# 1-Schematic_EmbeddedLab.net
KiCad netlist of a schematic drawn in EasyEDA
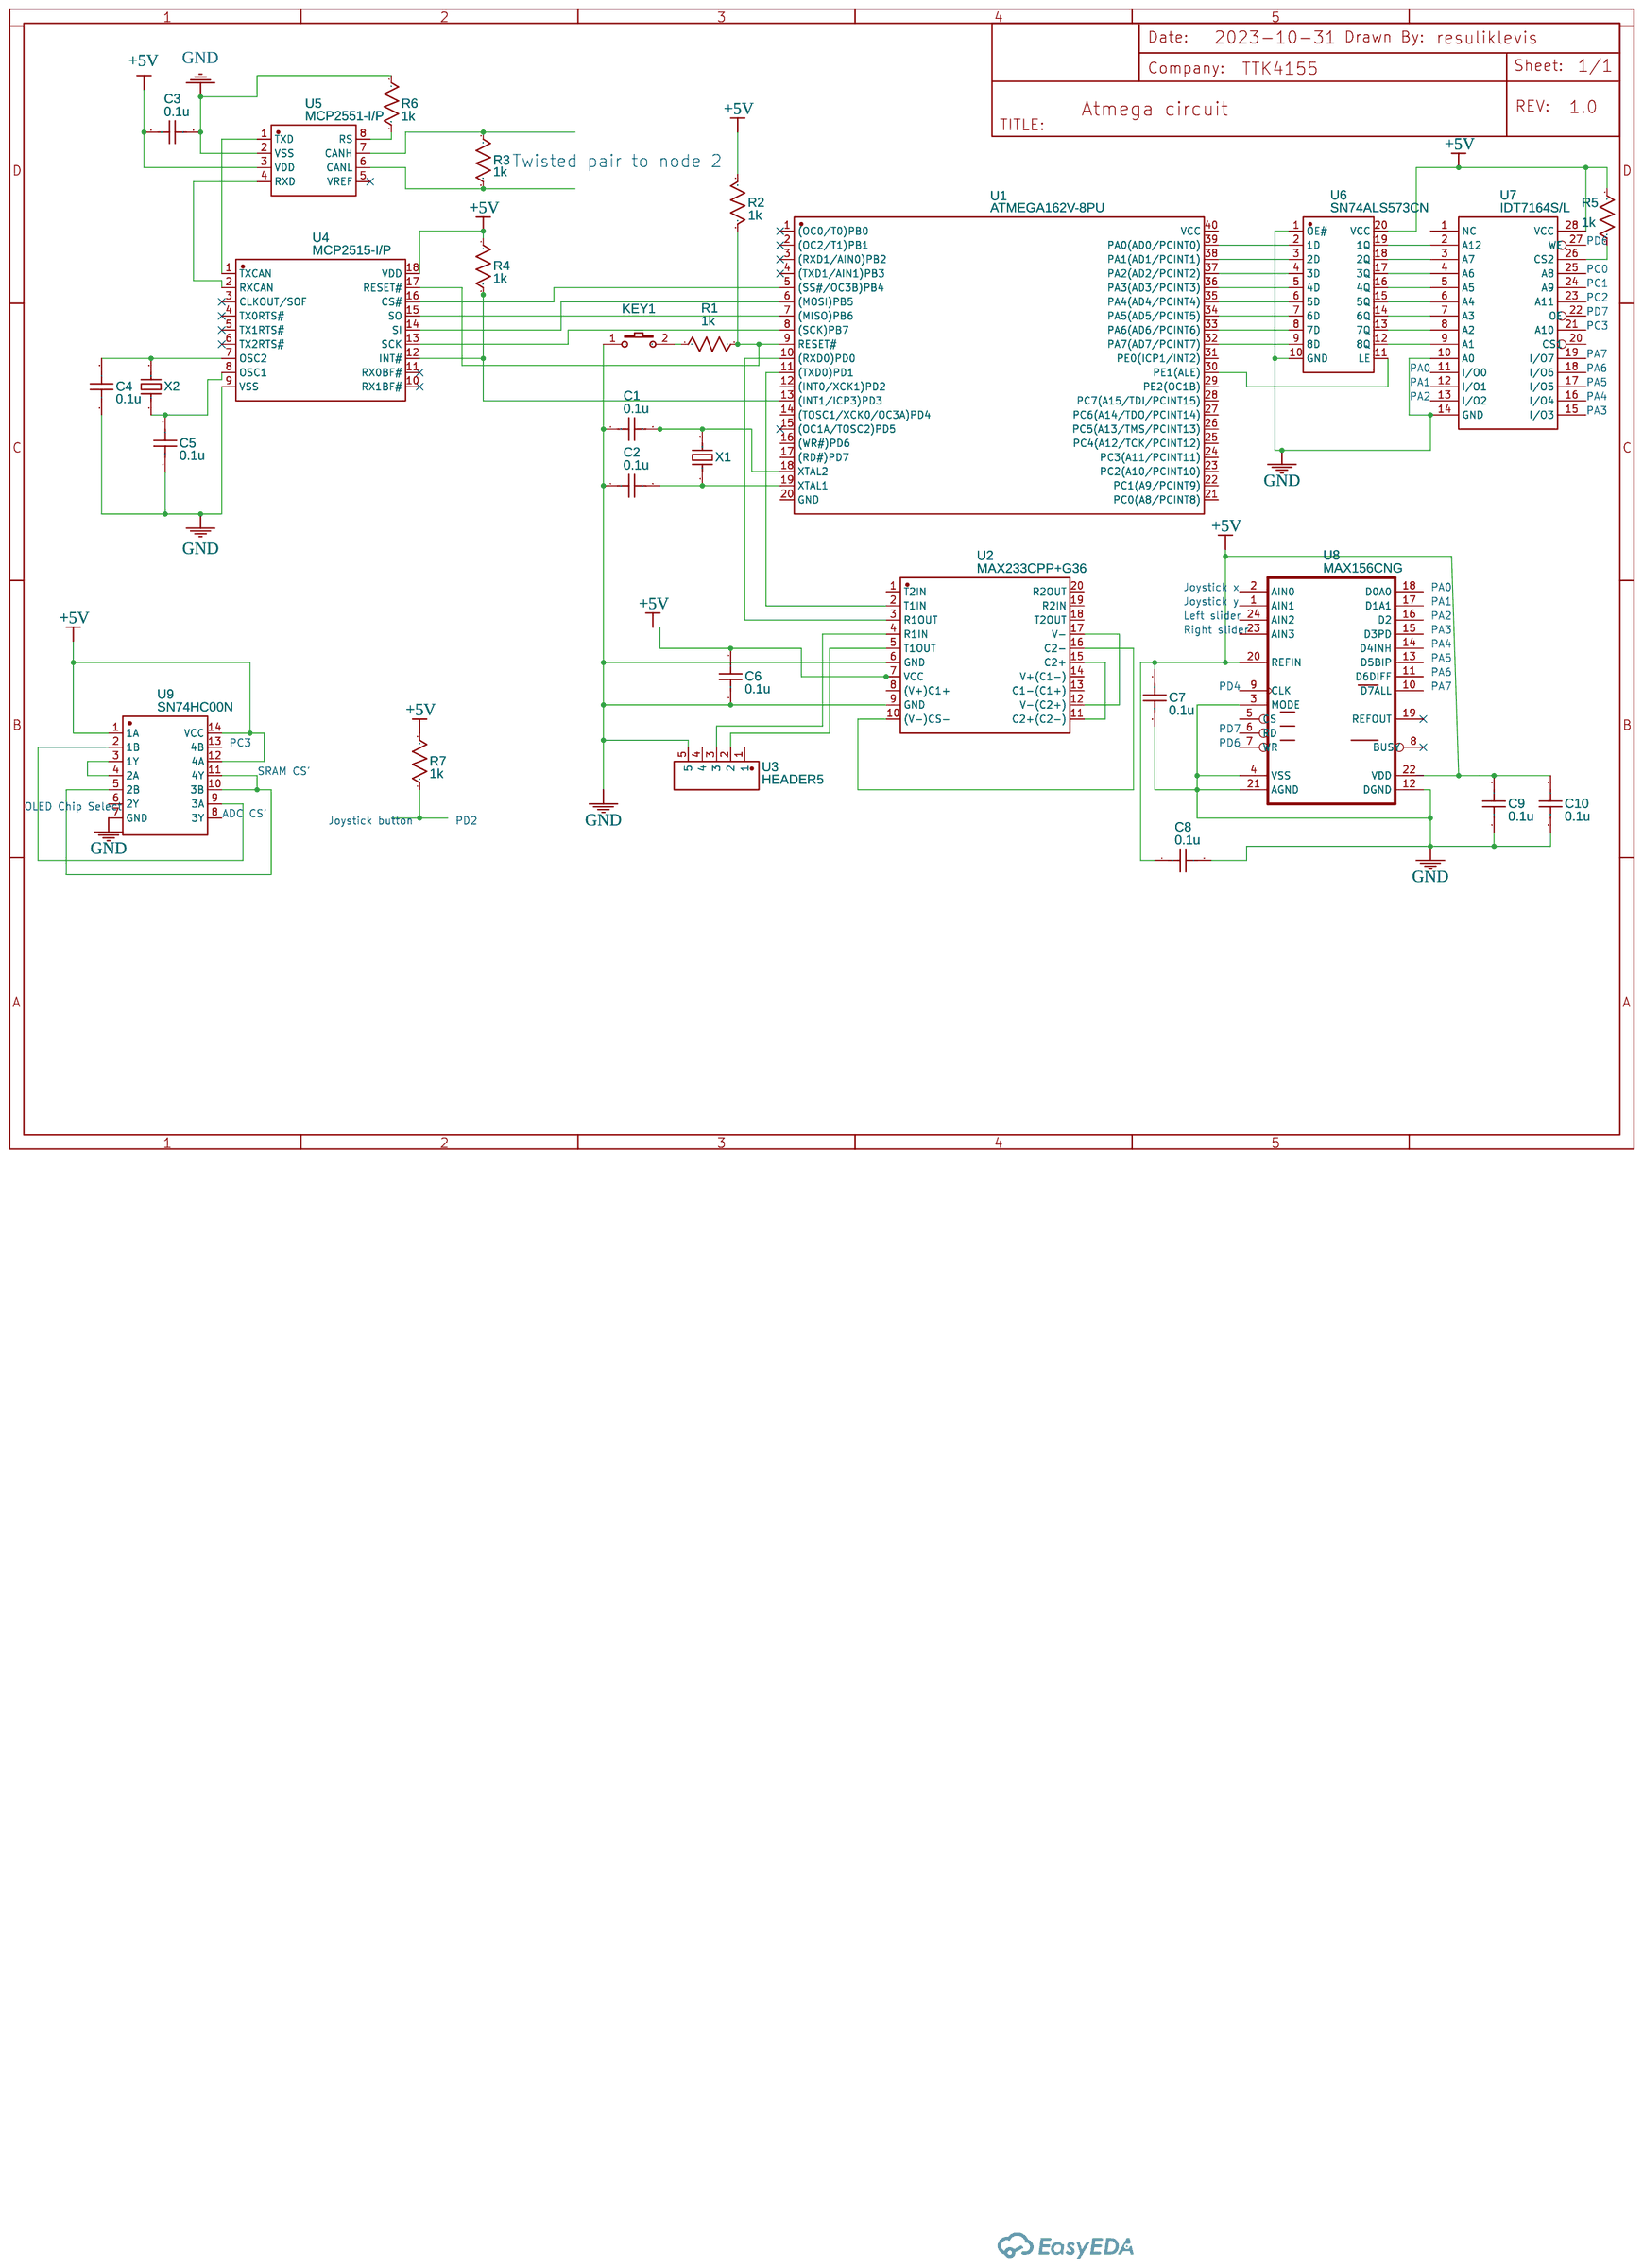
[diagram p0: schematic sheet]

(export (version "E")
  (design (tool "Eeschema 10.0.6"))
  (components
    (comp (ref "C1") (value "0.1u") (libsource (lib "") (part "C_0603_US_2")))
    (comp (ref "C2") (value "0.1u") (libsource (lib "") (part "C_0603_US_2")))
    (comp (ref "C3") (value "0.1u") (libsource (lib "") (part "C_0603_US_2")))
    (comp (ref "C4") (value "0.1u") (libsource (lib "") (part "C_0603_US_1")))
    (comp (ref "C5") (value "0.1u") (libsource (lib "") (part "C_0603_US_1")))
    (comp (ref "C6") (value "0.1u") (libsource (lib "") (part "C_0603_US")))
    (comp (ref "C7") (value "0.1u") (libsource (lib "") (part "C_0603_US")))
    (comp (ref "C8") (value "0.1u") (libsource (lib "") (part "C_0603_US_2")))
    (comp (ref "C9") (value "0.1u") (libsource (lib "") (part "C_0603_US_1")))
    (comp (ref "C10") (value "0.1u") (libsource (lib "") (part "C_0603_US")))
    (comp (ref "KEY1")
      (value "K2-3.6×6.1_SMD")
      (fields (field (name "Manufacturer Part") "K2-1107ST-A4SW-06"))
      (libsource (lib "") (part "K2-3.6×6.1_SMD"))
    )
    (comp (ref "R1") (value "1k") (libsource (lib "") (part "R_0603_US_1")))
    (comp (ref "R2") (value "1k") (libsource (lib "") (part "R_0603_US_2")))
    (comp (ref "R3") (value "1k") (libsource (lib "") (part "R_0603_US")))
    (comp (ref "R4") (value "1k") (libsource (lib "") (part "R_0603_US")))
    (comp (ref "R5") (value "1k") (libsource (lib "") (part "R_0603_US")))
    (comp (ref "R6") (value "1k") (libsource (lib "") (part "R_0603_US")))
    (comp (ref "R7") (value "1k") (libsource (lib "") (part "R_0603_US_3")))
    (comp (ref "U1")
      (value "ATMEGA162V-8PU")
      (fields (field (name "Manufacturer") "MICROCHIP(美国微芯)"))
      (libsource (lib "") (part "ATMEGA162V-8PU"))
    )
    (comp (ref "U2")
      (value "MAX233CPP+G36")
      (fields (field (name "Manufacturer") "MAXIM(美信)"))
      (libsource (lib "") (part "MAX233CPP+G36"))
    )
    (comp (ref "U3")
      (value "HEADER5")
      (fields (field (name "Manufacturer Part") "Header5"))
      (libsource (lib "") (part "HEADER5"))
    )
    (comp (ref "U4")
      (value "MCP2515-I/P")
      (fields (field (name "Manufacturer") "MICROCHIP(美国微芯)"))
      (libsource (lib "") (part "MCP2515-I/P"))
    )
    (comp (ref "U5")
      (value "MCP2551-I/P")
      (fields (field (name "Manufacturer") "MICROCHIP(美国微芯)"))
      (libsource (lib "") (part "MCP2551-I/P"))
    )
    (comp (ref "U6")
      (value "SN74ALS573CN")
      (fields (field (name "Manufacturer") "TI(德州仪器)"))
      (libsource (lib "") (part "SN74ALS573CN"))
    )
    (comp (ref "U7") (value "IDT7164S/L") (libsource (lib "") (part "IDT7164S/L")))
    (comp (ref "U8") (value "MAX156CNG") (libsource (lib "") (part "MAX156CNG")))
    (comp (ref "U9")
      (value "SN74HC00N")
      (fields (field (name "Manufacturer") "TI"))
      (libsource (lib "") (part "SN74HC00N"))
    )
    (comp (ref "X1") (value "SMD-2_5032-48M") (libsource (lib "") (part "SMD-2_5032-48M")))
    (comp (ref "X2") (value "SMD-2_5032-48M") (libsource (lib "") (part "SMD-2_5032-48M")))
  )
  (nets
    (net (code "1") (name "+5V") (class "Default")
      (node (ref "C10") (pin "1") (pinfunction "1_1") (pintype "unspecified"))
      (node (ref "C3") (pin "1") (pinfunction "1_1") (pintype "unspecified"))
      (node (ref "C7") (pin "1") (pinfunction "1_1") (pintype "unspecified"))
      (node (ref "C8") (pin "1") (pinfunction "1_1") (pintype "unspecified"))
      (node (ref "C9") (pin "2") (pinfunction "2_2") (pintype "unspecified"))
      (node (ref "R2") (pin "2") (pinfunction "2_2") (pintype "unspecified"))
      (node (ref "R4") (pin "1") (pinfunction "1_1") (pintype "unspecified"))
      (node (ref "R5") (pin "1") (pinfunction "1_1") (pintype "unspecified"))
      (node (ref "R7") (pin "2") (pinfunction "2_2") (pintype "unspecified"))
      (node (ref "U4") (pin "18") (pinfunction "VDD_18") (pintype "unspecified"))
      (node (ref "U5") (pin "3") (pinfunction "VDD_3") (pintype "unspecified"))
      (node (ref "U6") (pin "20") (pinfunction "VCC_20") (pintype "unspecified"))
      (node (ref "U7") (pin "28") (pinfunction "VCC_28") (pintype "unspecified"))
      (node (ref "U8") (pin "20") (pinfunction "REFIN_20") (pintype "input"))
      (node (ref "U8") (pin "22") (pinfunction "VDD_22") (pintype "passive"))
      (node (ref "U9") (pin "1") (pinfunction "1A_1") (pintype "unspecified"))
      (node (ref "U9") (pin "12") (pinfunction "4A_12") (pintype "unspecified"))
      (node (ref "U9") (pin "14") (pinfunction "VCC_14") (pintype "unspecified"))
    )
    (net (code "2") (name "GND") (class "Default")
      (node (ref "C1") (pin "1") (pinfunction "1_1") (pintype "unspecified"))
      (node (ref "C10") (pin "2") (pinfunction "2_2") (pintype "unspecified"))
      (node (ref "C2") (pin "1") (pinfunction "1_1") (pintype "unspecified"))
      (node (ref "C3") (pin "2") (pinfunction "2_2") (pintype "unspecified"))
      (node (ref "C4") (pin "1") (pinfunction "1_1") (pintype "unspecified"))
      (node (ref "C5") (pin "1") (pinfunction "1_1") (pintype "unspecified"))
      (node (ref "C6") (pin "2") (pinfunction "2_2") (pintype "unspecified"))
      (node (ref "C7") (pin "2") (pinfunction "2_2") (pintype "unspecified"))
      (node (ref "C8") (pin "2") (pinfunction "2_2") (pintype "unspecified"))
      (node (ref "C9") (pin "1") (pinfunction "1_1") (pintype "unspecified"))
      (node (ref "KEY1") (pin "1") (pinfunction "1_1") (pintype "unspecified"))
      (node (ref "R6") (pin "1") (pinfunction "1_1") (pintype "unspecified"))
      (node (ref "U2") (pin "6") (pinfunction "GND_6") (pintype "unspecified"))
      (node (ref "U2") (pin "9") (pinfunction "GND_9") (pintype "unspecified"))
      (node (ref "U3") (pin "5") (pinfunction "5_5") (pintype "unspecified"))
      (node (ref "U4") (pin "9") (pinfunction "VSS_9") (pintype "unspecified"))
      (node (ref "U5") (pin "2") (pinfunction "VSS_2") (pintype "unspecified"))
      (node (ref "U6") (pin "1") (pinfunction "OE#_1") (pintype "unspecified"))
      (node (ref "U6") (pin "10") (pinfunction "GND_10") (pintype "unspecified"))
      (node (ref "U7") (pin "10") (pinfunction "A0_10") (pintype "unspecified"))
      (node (ref "U7") (pin "14") (pinfunction "GND_14") (pintype "unspecified"))
      (node (ref "U8") (pin "12") (pinfunction "DGND_12") (pintype "passive"))
      (node (ref "U8") (pin "21") (pinfunction "AGND_21") (pintype "passive"))
      (node (ref "U8") (pin "3") (pinfunction "MODE_3") (pintype "input"))
      (node (ref "U8") (pin "4") (pinfunction "VSS_4") (pintype "passive"))
      (node (ref "U9") (pin "7") (pinfunction "GND_7") (pintype "unspecified"))
    )
    (net (code "3") (name "Net-(KEY1-Pad2)") (class "Default")
      (node (ref "KEY1") (pin "2") (pinfunction "2_2") (pintype "unspecified"))
      (node (ref "R1") (pin "1") (pinfunction "1_1") (pintype "unspecified"))
    )
    (net (code "4") (name "Net-(U1-(INT1{slash}ICP3)PD3)") (class "Default")
      (node (ref "R4") (pin "2") (pinfunction "2_2") (pintype "unspecified"))
      (node (ref "U1") (pin "13") (pinfunction "(INT1/ICP3)PD3_13") (pintype "unspecified"))
      (node (ref "U4") (pin "12") (pinfunction "INT#_12") (pintype "unspecified"))
    )
    (net (code "5") (name "Net-(U1-(MISO)PB6)") (class "Default")
      (node (ref "U1") (pin "7") (pinfunction "(MISO)PB6_7") (pintype "unspecified"))
      (node (ref "U4") (pin "15") (pinfunction "SO_15") (pintype "unspecified"))
    )
    (net (code "6") (name "Net-(U1-(MOSI)PB5)") (class "Default")
      (node (ref "U1") (pin "6") (pinfunction "(MOSI)PB5_6") (pintype "unspecified"))
      (node (ref "U4") (pin "14") (pinfunction "SI_14") (pintype "unspecified"))
    )
    (net (code "7") (name "Net-(U1-(RXD0)PD0)") (class "Default")
      (node (ref "U1") (pin "10") (pinfunction "(RXD0)PD0_10") (pintype "unspecified"))
      (node (ref "U2") (pin "3") (pinfunction "R1OUT_3") (pintype "unspecified"))
    )
    (net (code "8") (name "Net-(U1-(SCK)PB7)") (class "Default")
      (node (ref "U1") (pin "8") (pinfunction "(SCK)PB7_8") (pintype "unspecified"))
      (node (ref "U4") (pin "13") (pinfunction "SCK_13") (pintype "unspecified"))
    )
    (net (code "9") (name "Net-(U1-(SS#{slash}OC3B)PB4)") (class "Default")
      (node (ref "U1") (pin "5") (pinfunction "(SS#/OC3B)PB4_5") (pintype "unspecified"))
      (node (ref "U4") (pin "16") (pinfunction "CS#_16") (pintype "unspecified"))
    )
    (net (code "10") (name "Net-(U1-(TXD0)PD1)") (class "Default")
      (node (ref "U1") (pin "11") (pinfunction "(TXD0)PD1_11") (pintype "unspecified"))
      (node (ref "U2") (pin "2") (pinfunction "T1IN_2") (pintype "unspecified"))
    )
    (net (code "11") (name "Net-(U1-PA0(AD0{slash}PCINT0))") (class "Default")
      (node (ref "U1") (pin "39") (pinfunction "PA0(AD0/PCINT0)_39") (pintype "unspecified"))
      (node (ref "U6") (pin "2") (pinfunction "1D_2") (pintype "unspecified"))
    )
    (net (code "12") (name "Net-(U1-PA1(AD1{slash}PCINT1))") (class "Default")
      (node (ref "U1") (pin "38") (pinfunction "PA1(AD1/PCINT1)_38") (pintype "unspecified"))
      (node (ref "U6") (pin "3") (pinfunction "2D_3") (pintype "unspecified"))
    )
    (net (code "13") (name "Net-(U1-PA2(AD2{slash}PCINT2))") (class "Default")
      (node (ref "U1") (pin "37") (pinfunction "PA2(AD2/PCINT2)_37") (pintype "unspecified"))
      (node (ref "U6") (pin "4") (pinfunction "3D_4") (pintype "unspecified"))
    )
    (net (code "14") (name "Net-(U1-PA3(AD3{slash}PCINT3))") (class "Default")
      (node (ref "U1") (pin "36") (pinfunction "PA3(AD3/PCINT3)_36") (pintype "unspecified"))
      (node (ref "U6") (pin "5") (pinfunction "4D_5") (pintype "unspecified"))
    )
    (net (code "15") (name "Net-(U1-PA4(AD4{slash}PCINT4))") (class "Default")
      (node (ref "U1") (pin "35") (pinfunction "PA4(AD4/PCINT4)_35") (pintype "unspecified"))
      (node (ref "U6") (pin "6") (pinfunction "5D_6") (pintype "unspecified"))
    )
    (net (code "16") (name "Net-(U1-PA5(AD5{slash}PCINT5))") (class "Default")
      (node (ref "U1") (pin "34") (pinfunction "PA5(AD5/PCINT5)_34") (pintype "unspecified"))
      (node (ref "U6") (pin "7") (pinfunction "6D_7") (pintype "unspecified"))
    )
    (net (code "17") (name "Net-(U1-PA6(AD6{slash}PCINT6))") (class "Default")
      (node (ref "U1") (pin "33") (pinfunction "PA6(AD6/PCINT6)_33") (pintype "unspecified"))
      (node (ref "U6") (pin "8") (pinfunction "7D_8") (pintype "unspecified"))
    )
    (net (code "18") (name "Net-(U1-PA7(AD7{slash}PCINT7))") (class "Default")
      (node (ref "U1") (pin "32") (pinfunction "PA7(AD7/PCINT7)_32") (pintype "unspecified"))
      (node (ref "U6") (pin "9") (pinfunction "8D_9") (pintype "unspecified"))
    )
    (net (code "19") (name "Net-(U1-PE1(ALE))") (class "Default")
      (node (ref "U1") (pin "30") (pinfunction "PE1(ALE)_30") (pintype "unspecified"))
      (node (ref "U6") (pin "11") (pinfunction "LE_11") (pintype "unspecified"))
    )
    (net (code "20") (name "Net-(U1-RESET#)") (class "Default")
      (node (ref "R1") (pin "2") (pinfunction "2_2") (pintype "unspecified"))
      (node (ref "R2") (pin "1") (pinfunction "1_1") (pintype "unspecified"))
      (node (ref "U1") (pin "9") (pinfunction "RESET#_9") (pintype "unspecified"))
      (node (ref "U4") (pin "17") (pinfunction "RESET#_17") (pintype "unspecified"))
    )
    (net (code "21") (name "Net-(U1-XTAL1)") (class "Default")
      (node (ref "C2") (pin "2") (pinfunction "2_2") (pintype "unspecified"))
      (node (ref "U1") (pin "19") (pinfunction "XTAL1_19") (pintype "unspecified"))
      (node (ref "X1") (pin "2") (pinfunction "2_2") (pintype "input"))
    )
    (net (code "22") (name "Net-(U1-XTAL2)") (class "Default")
      (node (ref "C1") (pin "2") (pinfunction "2_2") (pintype "unspecified"))
      (node (ref "U1") (pin "18") (pinfunction "XTAL2_18") (pintype "unspecified"))
      (node (ref "X1") (pin "1") (pinfunction "1_1") (pintype "input"))
    )
    (net (code "23") (name "Net-(U2-(V-)CS-)") (class "Default")
      (node (ref "U2") (pin "10") (pinfunction "(V-)CS-_10") (pintype "unspecified"))
      (node (ref "U2") (pin "16") (pinfunction "C2-_16") (pintype "unspecified"))
    )
    (net (code "24") (name "Net-(U2-C2+(C2-))") (class "Default")
      (node (ref "U2") (pin "11") (pinfunction "C2+(C2-)_11") (pintype "unspecified"))
      (node (ref "U2") (pin "15") (pinfunction "C2+_15") (pintype "unspecified"))
    )
    (net (code "25") (name "Net-(U2-R1IN)") (class "Default")
      (node (ref "U2") (pin "4") (pinfunction "R1IN_4") (pintype "unspecified"))
      (node (ref "U3") (pin "3") (pinfunction "3_3") (pintype "unspecified"))
    )
    (net (code "26") (name "Net-(U2-T1OUT)") (class "Default")
      (node (ref "U2") (pin "5") (pinfunction "T1OUT_5") (pintype "unspecified"))
      (node (ref "U3") (pin "2") (pinfunction "2_2") (pintype "unspecified"))
    )
    (net (code "27") (name "Net-(U2-V-(C2+))") (class "Default")
      (node (ref "U2") (pin "12") (pinfunction "V-(C2+)_12") (pintype "unspecified"))
      (node (ref "U2") (pin "17") (pinfunction "V-_17") (pintype "unspecified"))
    )
    (net (code "28") (name "Net-(U2-VCC)") (class "Default")
      (node (ref "C6") (pin "1") (pinfunction "1_1") (pintype "unspecified"))
      (node (ref "U2") (pin "7") (pinfunction "VCC_7") (pintype "unspecified"))
    )
    (net (code "29") (name "Net-(U4-OSC1)") (class "Default")
      (node (ref "C5") (pin "2") (pinfunction "2_2") (pintype "unspecified"))
      (node (ref "U4") (pin "8") (pinfunction "OSC1_8") (pintype "unspecified"))
      (node (ref "X2") (pin "2") (pinfunction "2_2") (pintype "input"))
    )
    (net (code "30") (name "Net-(U4-OSC2)") (class "Default")
      (node (ref "C4") (pin "2") (pinfunction "2_2") (pintype "unspecified"))
      (node (ref "U4") (pin "7") (pinfunction "OSC2_7") (pintype "unspecified"))
      (node (ref "X2") (pin "1") (pinfunction "1_1") (pintype "input"))
    )
    (net (code "31") (name "Net-(U4-RXCAN)") (class "Default")
      (node (ref "U4") (pin "2") (pinfunction "RXCAN_2") (pintype "unspecified"))
      (node (ref "U5") (pin "4") (pinfunction "RXD_4") (pintype "unspecified"))
    )
    (net (code "32") (name "Net-(U4-TXCAN)") (class "Default")
      (node (ref "U4") (pin "1") (pinfunction "TXCAN_1") (pintype "unspecified"))
      (node (ref "U5") (pin "1") (pinfunction "TXD_1") (pintype "unspecified"))
    )
    (net (code "33") (name "Net-(U5-CANH)") (class "Default")
      (node (ref "R3") (pin "1") (pinfunction "1_1") (pintype "unspecified"))
      (node (ref "U5") (pin "7") (pinfunction "CANH_7") (pintype "unspecified"))
    )
    (net (code "34") (name "Net-(U5-CANL)") (class "Default")
      (node (ref "R3") (pin "2") (pinfunction "2_2") (pintype "unspecified"))
      (node (ref "U5") (pin "6") (pinfunction "CANL_6") (pintype "unspecified"))
    )
    (net (code "35") (name "Net-(U5-RS)") (class "Default")
      (node (ref "R6") (pin "2") (pinfunction "2_2") (pintype "unspecified"))
      (node (ref "U5") (pin "8") (pinfunction "RS_8") (pintype "unspecified"))
    )
    (net (code "36") (name "Net-(U6-1Q)") (class "Default")
      (node (ref "U6") (pin "19") (pinfunction "1Q_19") (pintype "unspecified"))
      (node (ref "U7") (pin "2") (pinfunction "A12_2") (pintype "unspecified"))
    )
    (net (code "37") (name "Net-(U6-2Q)") (class "Default")
      (node (ref "U6") (pin "18") (pinfunction "2Q_18") (pintype "unspecified"))
      (node (ref "U7") (pin "3") (pinfunction "A7_3") (pintype "unspecified"))
    )
    (net (code "38") (name "Net-(U6-3Q)") (class "Default")
      (node (ref "U6") (pin "17") (pinfunction "3Q_17") (pintype "unspecified"))
      (node (ref "U7") (pin "4") (pinfunction "A6_4") (pintype "unspecified"))
    )
    (net (code "39") (name "Net-(U6-4Q)") (class "Default")
      (node (ref "U6") (pin "16") (pinfunction "4Q_16") (pintype "unspecified"))
      (node (ref "U7") (pin "5") (pinfunction "A5_5") (pintype "unspecified"))
    )
    (net (code "40") (name "Net-(U6-5Q)") (class "Default")
      (node (ref "U6") (pin "15") (pinfunction "5Q_15") (pintype "unspecified"))
      (node (ref "U7") (pin "6") (pinfunction "A4_6") (pintype "unspecified"))
    )
    (net (code "41") (name "Net-(U6-6Q)") (class "Default")
      (node (ref "U6") (pin "14") (pinfunction "6Q_14") (pintype "unspecified"))
      (node (ref "U7") (pin "7") (pinfunction "A3_7") (pintype "unspecified"))
    )
    (net (code "42") (name "Net-(U6-7Q)") (class "Default")
      (node (ref "U6") (pin "13") (pinfunction "7Q_13") (pintype "unspecified"))
      (node (ref "U7") (pin "8") (pinfunction "A2_8") (pintype "unspecified"))
    )
    (net (code "43") (name "Net-(U6-8Q)") (class "Default")
      (node (ref "U6") (pin "12") (pinfunction "8Q_12") (pintype "unspecified"))
      (node (ref "U7") (pin "9") (pinfunction "A1_9") (pintype "unspecified"))
    )
    (net (code "44") (name "Net-(U7-CS2)") (class "Default")
      (node (ref "R5") (pin "2") (pinfunction "2_2") (pintype "unspecified"))
      (node (ref "U7") (pin "26") (pinfunction "CS2_26") (pintype "unspecified"))
    )
    (net (code "45") (name "Net-(U9-1B)") (class "Default")
      (node (ref "U9") (pin "2") (pinfunction "1B_2") (pintype "unspecified"))
      (node (ref "U9") (pin "9") (pinfunction "3A_9") (pintype "unspecified"))
    )
    (net (code "46") (name "Net-(U9-1Y)") (class "Default")
      (node (ref "U9") (pin "3") (pinfunction "1Y_3") (pintype "unspecified"))
      (node (ref "U9") (pin "4") (pinfunction "2A_4") (pintype "unspecified"))
    )
    (net (code "47") (name "Net-(U9-2B)") (class "Default")
      (node (ref "U9") (pin "10") (pinfunction "3B_10") (pintype "unspecified"))
      (node (ref "U9") (pin "11") (pinfunction "4Y_11") (pintype "unspecified"))
      (node (ref "U9") (pin "5") (pinfunction "2B_5") (pintype "unspecified"))
    )
    (net (code "48") (name "unconnected-(R7-Pad1)") (class "Default")
      (node (ref "R7") (pin "1") (pinfunction "1_1") (pintype "unspecified"))
    )
    (net (code "49") (name "unconnected-(U1-(INT0{slash}XCK1)PD2-Pad12)") (class "Default")
      (node (ref "U1") (pin "12") (pinfunction "(INT0/XCK1)PD2_12") (pintype "unspecified"))
    )
    (net (code "50") (name "unconnected-(U1-(OC0{slash}T0)PB0-Pad1)") (class "Default")
      (node (ref "U1") (pin "1") (pinfunction "(OC0/T0)PB0_1") (pintype "unspecified+no_connect"))
    )
    (net (code "51") (name "unconnected-(U1-(OC1A{slash}TOSC2)PD5-Pad15)") (class "Default")
      (node (ref "U1") (pin "15") (pinfunction "(OC1A/TOSC2)PD5_15") (pintype "unspecified+no_connect"))
    )
    (net (code "52") (name "unconnected-(U1-(OC2{slash}T1)PB1-Pad2)") (class "Default")
      (node (ref "U1") (pin "2") (pinfunction "(OC2/T1)PB1_2") (pintype "unspecified+no_connect"))
    )
    (net (code "53") (name "unconnected-(U1-(RD#)PD7-Pad17)") (class "Default")
      (node (ref "U1") (pin "17") (pinfunction "(RD#)PD7_17") (pintype "unspecified"))
    )
    (net (code "54") (name "unconnected-(U1-(RXD1{slash}AIN0)PB2-Pad3)") (class "Default")
      (node (ref "U1") (pin "3") (pinfunction "(RXD1/AIN0)PB2_3") (pintype "unspecified+no_connect"))
    )
    (net (code "55") (name "unconnected-(U1-(TOSC1{slash}XCK0{slash}OC3A)PD4-Pad14)") (class "Default")
      (node (ref "U1") (pin "14") (pinfunction "(TOSC1/XCK0/OC3A)PD4_14") (pintype "unspecified"))
    )
    (net (code "56") (name "unconnected-(U1-(TXD1{slash}AIN1)PB3-Pad4)") (class "Default")
      (node (ref "U1") (pin "4") (pinfunction "(TXD1/AIN1)PB3_4") (pintype "unspecified+no_connect"))
    )
    (net (code "57") (name "unconnected-(U1-(WR#)PD6-Pad16)") (class "Default")
      (node (ref "U1") (pin "16") (pinfunction "(WR#)PD6_16") (pintype "unspecified"))
    )
    (net (code "58") (name "unconnected-(U1-GND-Pad20)") (class "Default")
      (node (ref "U1") (pin "20") (pinfunction "GND_20") (pintype "unspecified"))
    )
    (net (code "59") (name "unconnected-(U1-PC0(A8{slash}PCINT8)-Pad21)") (class "Default")
      (node (ref "U1") (pin "21") (pinfunction "PC0(A8/PCINT8)_21") (pintype "unspecified"))
    )
    (net (code "60") (name "unconnected-(U1-PC1(A9{slash}PCINT9)-Pad22)") (class "Default")
      (node (ref "U1") (pin "22") (pinfunction "PC1(A9/PCINT9)_22") (pintype "unspecified"))
    )
    (net (code "61") (name "unconnected-(U1-PC2(A10{slash}PCINT10)-Pad23)") (class "Default")
      (node (ref "U1") (pin "23") (pinfunction "PC2(A10/PCINT10)_23") (pintype "unspecified"))
    )
    (net (code "62") (name "unconnected-(U1-PC3(A11{slash}PCINT11)-Pad24)") (class "Default")
      (node (ref "U1") (pin "24") (pinfunction "PC3(A11/PCINT11)_24") (pintype "unspecified"))
    )
    (net (code "63") (name "unconnected-(U1-PC4(A12{slash}TCK{slash}PCINT12)-Pad25)") (class "Default")
      (node (ref "U1") (pin "25") (pinfunction "PC4(A12/TCK/PCINT12)_25") (pintype "unspecified"))
    )
    (net (code "64") (name "unconnected-(U1-PC5(A13{slash}TMS{slash}PCINT13)-Pad26)") (class "Default")
      (node (ref "U1") (pin "26") (pinfunction "PC5(A13/TMS/PCINT13)_26") (pintype "unspecified"))
    )
    (net (code "65") (name "unconnected-(U1-PC6(A14{slash}TDO{slash}PCINT14)-Pad27)") (class "Default")
      (node (ref "U1") (pin "27") (pinfunction "PC6(A14/TDO/PCINT14)_27") (pintype "unspecified"))
    )
    (net (code "66") (name "unconnected-(U1-PC7(A15{slash}TDI{slash}PCINT15)-Pad28)") (class "Default")
      (node (ref "U1") (pin "28") (pinfunction "PC7(A15/TDI/PCINT15)_28") (pintype "unspecified"))
    )
    (net (code "67") (name "unconnected-(U1-PE0(ICP1{slash}INT2)-Pad31)") (class "Default")
      (node (ref "U1") (pin "31") (pinfunction "PE0(ICP1/INT2)_31") (pintype "unspecified"))
    )
    (net (code "68") (name "unconnected-(U1-PE2(OC1B)-Pad29)") (class "Default")
      (node (ref "U1") (pin "29") (pinfunction "PE2(OC1B)_29") (pintype "unspecified"))
    )
    (net (code "69") (name "unconnected-(U1-VCC-Pad40)") (class "Default")
      (node (ref "U1") (pin "40") (pinfunction "VCC_40") (pintype "unspecified"))
    )
    (net (code "70") (name "unconnected-(U2-(V+)C1+-Pad8)") (class "Default")
      (node (ref "U2") (pin "8") (pinfunction "(V+)C1+_8") (pintype "unspecified"))
    )
    (net (code "71") (name "unconnected-(U2-C1-(C1+)-Pad13)") (class "Default")
      (node (ref "U2") (pin "13") (pinfunction "C1-(C1+)_13") (pintype "unspecified"))
    )
    (net (code "72") (name "unconnected-(U2-R2IN-Pad19)") (class "Default")
      (node (ref "U2") (pin "19") (pinfunction "R2IN_19") (pintype "unspecified"))
    )
    (net (code "73") (name "unconnected-(U2-R2OUT-Pad20)") (class "Default")
      (node (ref "U2") (pin "20") (pinfunction "R2OUT_20") (pintype "unspecified"))
    )
    (net (code "74") (name "unconnected-(U2-T2IN-Pad1)") (class "Default")
      (node (ref "U2") (pin "1") (pinfunction "T2IN_1") (pintype "unspecified"))
    )
    (net (code "75") (name "unconnected-(U2-T2OUT-Pad18)") (class "Default")
      (node (ref "U2") (pin "18") (pinfunction "T2OUT_18") (pintype "unspecified"))
    )
    (net (code "76") (name "unconnected-(U2-V+(C1-)-Pad14)") (class "Default")
      (node (ref "U2") (pin "14") (pinfunction "V+(C1-)_14") (pintype "unspecified"))
    )
    (net (code "77") (name "unconnected-(U3-Pad1)") (class "Default")
      (node (ref "U3") (pin "1") (pinfunction "1_1") (pintype "unspecified"))
    )
    (net (code "78") (name "unconnected-(U3-Pad4)") (class "Default")
      (node (ref "U3") (pin "4") (pinfunction "4_4") (pintype "unspecified"))
    )
    (net (code "79") (name "unconnected-(U4-CLKOUT{slash}SOF-Pad3)") (class "Default")
      (node (ref "U4") (pin "3") (pinfunction "CLKOUT/SOF_3") (pintype "unspecified+no_connect"))
    )
    (net (code "80") (name "unconnected-(U4-RX0BF#-Pad11)") (class "Default")
      (node (ref "U4") (pin "11") (pinfunction "RX0BF#_11") (pintype "unspecified+no_connect"))
    )
    (net (code "81") (name "unconnected-(U4-RX1BF#-Pad10)") (class "Default")
      (node (ref "U4") (pin "10") (pinfunction "RX1BF#_10") (pintype "unspecified+no_connect"))
    )
    (net (code "82") (name "unconnected-(U4-TX0RTS#-Pad4)") (class "Default")
      (node (ref "U4") (pin "4") (pinfunction "TX0RTS#_4") (pintype "unspecified+no_connect"))
    )
    (net (code "83") (name "unconnected-(U4-TX1RTS#-Pad5)") (class "Default")
      (node (ref "U4") (pin "5") (pinfunction "TX1RTS#_5") (pintype "unspecified+no_connect"))
    )
    (net (code "84") (name "unconnected-(U4-TX2RTS#-Pad6)") (class "Default")
      (node (ref "U4") (pin "6") (pinfunction "TX2RTS#_6") (pintype "unspecified+no_connect"))
    )
    (net (code "85") (name "unconnected-(U5-VREF-Pad5)") (class "Default")
      (node (ref "U5") (pin "5") (pinfunction "VREF_5") (pintype "unspecified+no_connect"))
    )
    (net (code "86") (name "unconnected-(U7-A8-Pad25)") (class "Default")
      (node (ref "U7") (pin "25") (pinfunction "A8_25") (pintype "unspecified"))
    )
    (net (code "87") (name "unconnected-(U7-A9-Pad24)") (class "Default")
      (node (ref "U7") (pin "24") (pinfunction "A9_24") (pintype "unspecified"))
    )
    (net (code "88") (name "unconnected-(U7-A10-Pad21)") (class "Default")
      (node (ref "U7") (pin "21") (pinfunction "A10_21") (pintype "unspecified"))
    )
    (net (code "89") (name "unconnected-(U7-A11-Pad23)") (class "Default")
      (node (ref "U7") (pin "23") (pinfunction "A11_23") (pintype "unspecified"))
    )
    (net (code "90") (name "unconnected-(U7-CS1-Pad20)") (class "Default")
      (node (ref "U7") (pin "20") (pinfunction "CS1_20") (pintype "unspecified"))
    )
    (net (code "91") (name "unconnected-(U7-I{slash}O0-Pad11)") (class "Default")
      (node (ref "U7") (pin "11") (pinfunction "I/O0_11") (pintype "unspecified"))
    )
    (net (code "92") (name "unconnected-(U7-I{slash}O1-Pad12)") (class "Default")
      (node (ref "U7") (pin "12") (pinfunction "I/O1_12") (pintype "unspecified"))
    )
    (net (code "93") (name "unconnected-(U7-I{slash}O2-Pad13)") (class "Default")
      (node (ref "U7") (pin "13") (pinfunction "I/O2_13") (pintype "unspecified"))
    )
    (net (code "94") (name "unconnected-(U7-I{slash}O3-Pad15)") (class "Default")
      (node (ref "U7") (pin "15") (pinfunction "I/O3_15") (pintype "unspecified"))
    )
    (net (code "95") (name "unconnected-(U7-I{slash}O4-Pad16)") (class "Default")
      (node (ref "U7") (pin "16") (pinfunction "I/O4_16") (pintype "unspecified"))
    )
    (net (code "96") (name "unconnected-(U7-I{slash}O5-Pad17)") (class "Default")
      (node (ref "U7") (pin "17") (pinfunction "I/O5_17") (pintype "unspecified"))
    )
    (net (code "97") (name "unconnected-(U7-I{slash}O6-Pad18)") (class "Default")
      (node (ref "U7") (pin "18") (pinfunction "I/O6_18") (pintype "unspecified"))
    )
    (net (code "98") (name "unconnected-(U7-I{slash}O7-Pad19)") (class "Default")
      (node (ref "U7") (pin "19") (pinfunction "I/O7_19") (pintype "unspecified"))
    )
    (net (code "99") (name "unconnected-(U7-NC-Pad1)") (class "Default")
      (node (ref "U7") (pin "1") (pinfunction "NC_1") (pintype "unspecified"))
    )
    (net (code "100") (name "unconnected-(U7-OE-Pad22)") (class "Default")
      (node (ref "U7") (pin "22") (pinfunction "OE_22") (pintype "unspecified"))
    )
    (net (code "101") (name "unconnected-(U7-WE-Pad27)") (class "Default")
      (node (ref "U7") (pin "27") (pinfunction "WE_27") (pintype "unspecified"))
    )
    (net (code "102") (name "unconnected-(U8-AIN0-Pad2)") (class "Default")
      (node (ref "U8") (pin "2") (pinfunction "AIN0_2") (pintype "input"))
    )
    (net (code "103") (name "unconnected-(U8-AIN1-Pad1)") (class "Default")
      (node (ref "U8") (pin "1") (pinfunction "AIN1_1") (pintype "input"))
    )
    (net (code "104") (name "unconnected-(U8-AIN2-Pad24)") (class "Default")
      (node (ref "U8") (pin "24") (pinfunction "AIN2_24") (pintype "input"))
    )
    (net (code "105") (name "unconnected-(U8-AIN3-Pad23)") (class "Default")
      (node (ref "U8") (pin "23") (pinfunction "AIN3_23") (pintype "input"))
    )
    (net (code "106") (name "unconnected-(U8-BUSY-Pad8)") (class "Default")
      (node (ref "U8") (pin "8") (pinfunction "BUSY_8") (pintype "output+no_connect"))
    )
    (net (code "107") (name "unconnected-(U8-CLK-Pad9)") (class "Default")
      (node (ref "U8") (pin "9") (pinfunction "CLK_9") (pintype "input"))
    )
    (net (code "108") (name "unconnected-(U8-CS-Pad5)") (class "Default")
      (node (ref "U8") (pin "5") (pinfunction "CS_5") (pintype "input"))
    )
    (net (code "109") (name "unconnected-(U8-D0A0-Pad18)") (class "Default")
      (node (ref "U8") (pin "18") (pinfunction "D0A0_18") (pintype "output"))
    )
    (net (code "110") (name "unconnected-(U8-D1A1-Pad17)") (class "Default")
      (node (ref "U8") (pin "17") (pinfunction "D1A1_17") (pintype "output"))
    )
    (net (code "111") (name "unconnected-(U8-D2-Pad16)") (class "Default")
      (node (ref "U8") (pin "16") (pinfunction "D2_16") (pintype "output"))
    )
    (net (code "112") (name "unconnected-(U8-D3PD-Pad15)") (class "Default")
      (node (ref "U8") (pin "15") (pinfunction "D3PD_15") (pintype "output"))
    )
    (net (code "113") (name "unconnected-(U8-D4INH-Pad14)") (class "Default")
      (node (ref "U8") (pin "14") (pinfunction "D4INH_14") (pintype "output"))
    )
    (net (code "114") (name "unconnected-(U8-D5BIP-Pad13)") (class "Default")
      (node (ref "U8") (pin "13") (pinfunction "D5BIP_13") (pintype "output"))
    )
    (net (code "115") (name "unconnected-(U8-D6DIFF-Pad11)") (class "Default")
      (node (ref "U8") (pin "11") (pinfunction "D6DIFF_11") (pintype "output"))
    )
    (net (code "116") (name "unconnected-(U8-D7ALL-Pad10)") (class "Default")
      (node (ref "U8") (pin "10") (pinfunction "D7ALL_10") (pintype "output"))
    )
    (net (code "117") (name "unconnected-(U8-RD-Pad6)") (class "Default")
      (node (ref "U8") (pin "6") (pinfunction "RD_6") (pintype "input"))
    )
    (net (code "118") (name "unconnected-(U8-REFOUT-Pad19)") (class "Default")
      (node (ref "U8") (pin "19") (pinfunction "REFOUT_19") (pintype "output+no_connect"))
    )
    (net (code "119") (name "unconnected-(U8-WR-Pad7)") (class "Default")
      (node (ref "U8") (pin "7") (pinfunction "WR_7") (pintype "input"))
    )
    (net (code "120") (name "unconnected-(U9-2Y-Pad6)") (class "Default")
      (node (ref "U9") (pin "6") (pinfunction "2Y_6") (pintype "unspecified"))
    )
    (net (code "121") (name "unconnected-(U9-3Y-Pad8)") (class "Default")
      (node (ref "U9") (pin "8") (pinfunction "3Y_8") (pintype "unspecified"))
    )
    (net (code "122") (name "unconnected-(U9-4B-Pad13)") (class "Default")
      (node (ref "U9") (pin "13") (pinfunction "4B_13") (pintype "unspecified"))
    )
  )
)
